# balanceador.net
KiCad netlist of a schematic drawn in EAGLE
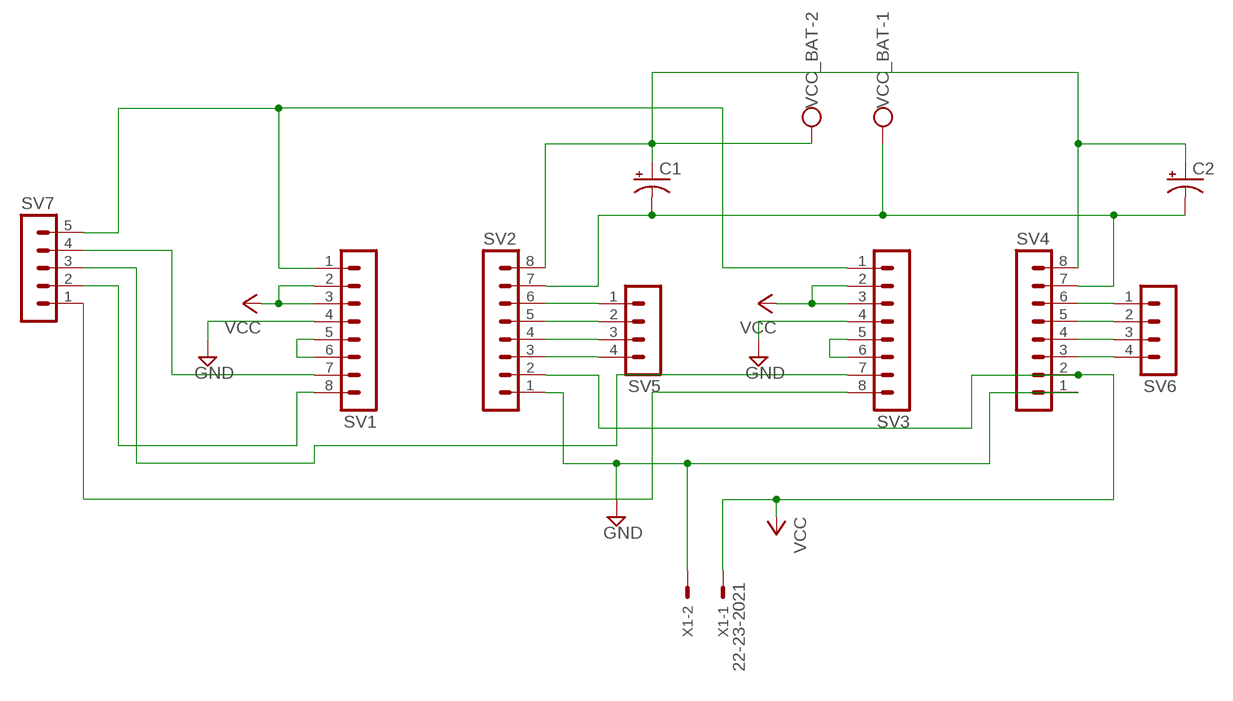
[diagram p0: schematic, sheet 1]

(export (version "E")
  (design (tool "Eeschema 10.0.6"))
  (components
    (comp (ref "C1")
      (value "CPOL-USE2.5-6")
      (footprint "eagle-import:E2,5-6")
      (libsource (lib "eagle-import") (part "CPOL-USE2.5-6"))
    )
    (comp (ref "C2")
      (value "CPOL-USE2.5-6")
      (footprint "eagle-import:E2,5-6")
      (libsource (lib "eagle-import") (part "CPOL-USE2.5-6"))
    )
    (comp (ref "SV1")
      (value "MA08-1")
      (footprint "eagle-import:MA08-1")
      (libsource (lib "eagle-import") (part "MA08-1"))
    )
    (comp (ref "SV2")
      (value "MA08-1")
      (footprint "eagle-import:MA08-1")
      (libsource (lib "eagle-import") (part "MA08-1"))
    )
    (comp (ref "SV3")
      (value "MA08-1")
      (footprint "eagle-import:MA08-1")
      (libsource (lib "eagle-import") (part "MA08-1"))
    )
    (comp (ref "SV4")
      (value "MA08-1")
      (footprint "eagle-import:MA08-1")
      (libsource (lib "eagle-import") (part "MA08-1"))
    )
    (comp (ref "SV5")
      (value "MA04-1")
      (footprint "eagle-import:MA04-1")
      (libsource (lib "eagle-import") (part "MA04-1"))
    )
    (comp (ref "SV6")
      (value "MA04-1")
      (footprint "eagle-import:MA04-1")
      (libsource (lib "eagle-import") (part "MA04-1"))
    )
    (comp (ref "SV7")
      (value "MA05-1")
      (footprint "eagle-import:MA05-1")
      (libsource (lib "eagle-import") (part "MA05-1"))
    )
    (comp (ref "VCC_BAT")
      (value "W237-102")
      (footprint "eagle-import:W237-102")
      (fields (field (name "MPN") "237-102"))
      (libsource (lib "eagle-import") (part "W237-102"))
    )
    (comp (ref "X1")
      (value "22-23-2021")
      (footprint "eagle-import:22-23-2021")
      (fields (field (name "MF") "MOLEX"))
      (libsource (lib "eagle-import") (part "22-23-2021"))
    )
  )
  (nets
    (net (code "1") (name "GND") (class "Default")
      (node (ref "SV1") (pin "4") (pinfunction "4_4") (pintype "passive"))
      (node (ref "SV2") (pin "1") (pinfunction "1_1") (pintype "passive"))
      (node (ref "SV3") (pin "4") (pinfunction "4_4") (pintype "passive"))
      (node (ref "SV4") (pin "1") (pinfunction "1_1") (pintype "passive"))
      (node (ref "X1") (pin "2") (pinfunction "S_2") (pintype "passive"))
    )
    (net (code "2") (name "Net-(SV1-Pad1)") (class "Default")
      (node (ref "SV1") (pin "1") (pinfunction "1_1") (pintype "passive"))
      (node (ref "SV3") (pin "1") (pinfunction "1_1") (pintype "passive"))
      (node (ref "SV7") (pin "5") (pinfunction "5_5") (pintype "passive"))
    )
    (net (code "3") (name "Net-(SV1-Pad5)") (class "Default")
      (node (ref "SV1") (pin "5") (pinfunction "5_5") (pintype "passive"))
      (node (ref "SV1") (pin "6") (pinfunction "6_6") (pintype "passive"))
    )
    (net (code "4") (name "Net-(SV1-Pad7)") (class "Default")
      (node (ref "SV1") (pin "7") (pinfunction "7_7") (pintype "passive"))
      (node (ref "SV7") (pin "4") (pinfunction "4_4") (pintype "passive"))
    )
    (net (code "5") (name "Net-(SV1-Pad8)") (class "Default")
      (node (ref "SV1") (pin "8") (pinfunction "8_8") (pintype "passive"))
      (node (ref "SV7") (pin "2") (pinfunction "2_2") (pintype "passive"))
    )
    (net (code "6") (name "Net-(SV2-Pad3)") (class "Default")
      (node (ref "SV2") (pin "3") (pinfunction "3_3") (pintype "passive"))
      (node (ref "SV5") (pin "4") (pinfunction "4_4") (pintype "passive"))
    )
    (net (code "7") (name "Net-(SV2-Pad4)") (class "Default")
      (node (ref "SV2") (pin "4") (pinfunction "4_4") (pintype "passive"))
      (node (ref "SV5") (pin "3") (pinfunction "3_3") (pintype "passive"))
    )
    (net (code "8") (name "Net-(SV2-Pad5)") (class "Default")
      (node (ref "SV2") (pin "5") (pinfunction "5_5") (pintype "passive"))
      (node (ref "SV5") (pin "2") (pinfunction "2_2") (pintype "passive"))
    )
    (net (code "9") (name "Net-(SV2-Pad6)") (class "Default")
      (node (ref "SV2") (pin "6") (pinfunction "6_6") (pintype "passive"))
      (node (ref "SV5") (pin "1") (pinfunction "1_1") (pintype "passive"))
    )
    (net (code "10") (name "Net-(SV3-Pad5)") (class "Default")
      (node (ref "SV3") (pin "5") (pinfunction "5_5") (pintype "passive"))
      (node (ref "SV3") (pin "6") (pinfunction "6_6") (pintype "passive"))
    )
    (net (code "11") (name "Net-(SV3-Pad7)") (class "Default")
      (node (ref "SV3") (pin "7") (pinfunction "7_7") (pintype "passive"))
      (node (ref "SV7") (pin "3") (pinfunction "3_3") (pintype "passive"))
    )
    (net (code "12") (name "Net-(SV3-Pad8)") (class "Default")
      (node (ref "SV3") (pin "8") (pinfunction "8_8") (pintype "passive"))
      (node (ref "SV7") (pin "1") (pinfunction "1_1") (pintype "passive"))
    )
    (net (code "13") (name "Net-(SV4-Pad3)") (class "Default")
      (node (ref "SV4") (pin "3") (pinfunction "3_3") (pintype "passive"))
      (node (ref "SV6") (pin "4") (pinfunction "4_4") (pintype "passive"))
    )
    (net (code "14") (name "Net-(SV4-Pad4)") (class "Default")
      (node (ref "SV4") (pin "4") (pinfunction "4_4") (pintype "passive"))
      (node (ref "SV6") (pin "3") (pinfunction "3_3") (pintype "passive"))
    )
    (net (code "15") (name "Net-(SV4-Pad5)") (class "Default")
      (node (ref "SV4") (pin "5") (pinfunction "5_5") (pintype "passive"))
      (node (ref "SV6") (pin "2") (pinfunction "2_2") (pintype "passive"))
    )
    (net (code "16") (name "Net-(SV4-Pad6)") (class "Default")
      (node (ref "SV4") (pin "6") (pinfunction "6_6") (pintype "passive"))
      (node (ref "SV6") (pin "1") (pinfunction "1_1") (pintype "passive"))
    )
    (net (code "17") (name "Net-(VCC_BATA-KL)") (class "Default")
      (node (ref "C1") (pin "-") (pinfunction "-_-") (pintype "passive"))
      (node (ref "C2") (pin "-") (pinfunction "-_-") (pintype "passive"))
      (node (ref "SV2") (pin "7") (pinfunction "7_7") (pintype "passive"))
      (node (ref "SV4") (pin "7") (pinfunction "7_7") (pintype "passive"))
      (node (ref "VCC_BAT") (pin "1") (pinfunction "KL_1") (pintype "passive"))
    )
    (net (code "18") (name "Net-(VCC_BATB-KL)") (class "Default")
      (node (ref "C1") (pin "+") (pinfunction "+_+") (pintype "passive"))
      (node (ref "C2") (pin "+") (pinfunction "+_+") (pintype "passive"))
      (node (ref "SV2") (pin "8") (pinfunction "8_8") (pintype "passive"))
      (node (ref "SV4") (pin "8") (pinfunction "8_8") (pintype "passive"))
      (node (ref "VCC_BAT") (pin "2") (pinfunction "KL_2") (pintype "passive"))
    )
    (net (code "19") (name "VCC") (class "Default")
      (node (ref "SV1") (pin "2") (pinfunction "2_2") (pintype "passive"))
      (node (ref "SV1") (pin "3") (pinfunction "3_3") (pintype "passive"))
      (node (ref "SV2") (pin "2") (pinfunction "2_2") (pintype "passive"))
      (node (ref "SV3") (pin "2") (pinfunction "2_2") (pintype "passive"))
      (node (ref "SV3") (pin "3") (pinfunction "3_3") (pintype "passive"))
      (node (ref "SV4") (pin "2") (pinfunction "2_2") (pintype "passive"))
      (node (ref "X1") (pin "1") (pinfunction "S_1") (pintype "passive"))
    )
  )
)
